# 737NG_CDU_SidePanel_v_01.net
KiCad netlist of a schematic drawn in EasyEDA
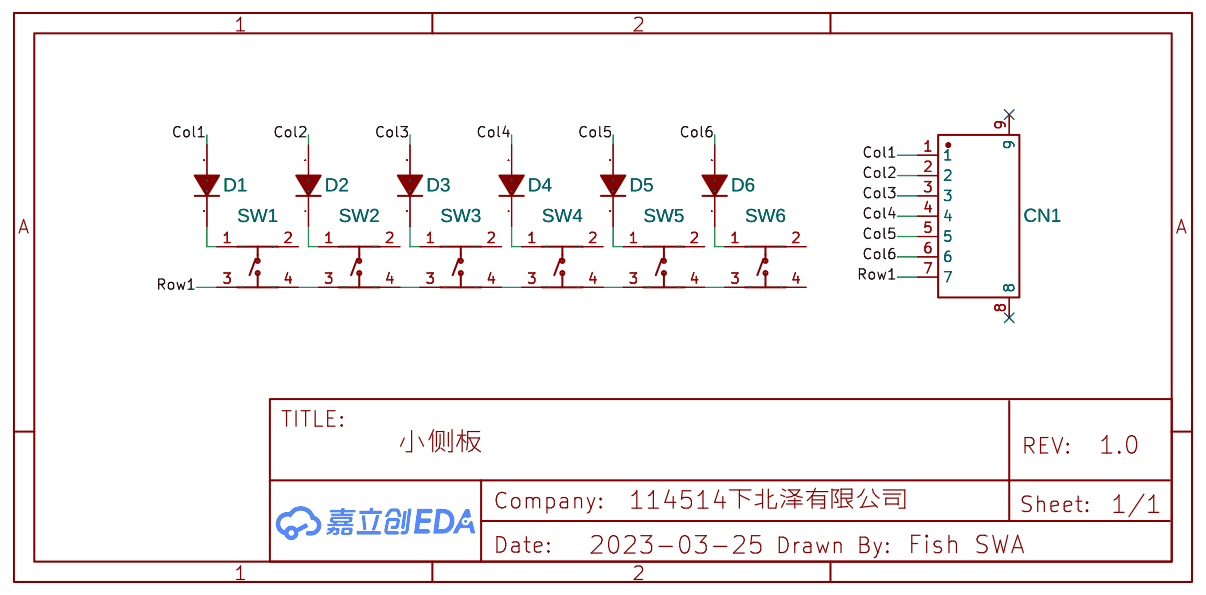
[diagram p0: schematic sheet]

(export (version "E")
  (design (tool "Eeschema 10.0.6"))
  (components
    (comp (ref "CN1")
      (value "A1002WR-S-7P")
      (fields (field (name "BOM_Supplier Part") "C239525"))
      (libsource (lib "") (part "A1002WR-S-7P"))
    )
    (comp (ref "D1")
      (value "1N4148WS T4")
      (fields (field (name "BOM_Manufacturer Part") "1N4148WS") (field (name "BOM_Supplier Part") "C2128"))
      (libsource (lib "") (part "1N4148WS T4"))
    )
    (comp (ref "D2")
      (value "1N4148WS T4")
      (fields (field (name "BOM_Manufacturer Part") "1N4148WS") (field (name "BOM_Supplier Part") "C2128"))
      (libsource (lib "") (part "1N4148WS T4"))
    )
    (comp (ref "D3")
      (value "1N4148WS T4")
      (fields (field (name "BOM_Manufacturer Part") "1N4148WS") (field (name "BOM_Supplier Part") "C2128"))
      (libsource (lib "") (part "1N4148WS T4"))
    )
    (comp (ref "D4")
      (value "1N4148WS T4")
      (fields (field (name "BOM_Manufacturer Part") "1N4148WS") (field (name "BOM_Supplier Part") "C2128"))
      (libsource (lib "") (part "1N4148WS T4"))
    )
    (comp (ref "D5")
      (value "1N4148WS T4")
      (fields (field (name "BOM_Manufacturer Part") "1N4148WS") (field (name "BOM_Supplier Part") "C2128"))
      (libsource (lib "") (part "1N4148WS T4"))
    )
    (comp (ref "D6")
      (value "1N4148WS T4")
      (fields (field (name "BOM_Manufacturer Part") "1N4148WS") (field (name "BOM_Supplier Part") "C2128"))
      (libsource (lib "") (part "1N4148WS T4"))
    )
    (comp (ref "SW1")
      (value "PTS525SM15SMTR2LFS")
      (fields (field (name "BOM_Supplier Part") "C221856"))
      (libsource (lib "") (part "PTS525SM15SMTR2LFS"))
    )
    (comp (ref "SW2")
      (value "PTS525SM15SMTR2LFS")
      (fields (field (name "BOM_Supplier Part") "C221856"))
      (libsource (lib "") (part "PTS525SM15SMTR2LFS"))
    )
    (comp (ref "SW3")
      (value "PTS525SM15SMTR2LFS")
      (fields (field (name "BOM_Supplier Part") "C221856"))
      (libsource (lib "") (part "PTS525SM15SMTR2LFS"))
    )
    (comp (ref "SW4")
      (value "PTS525SM15SMTR2LFS")
      (fields (field (name "BOM_Supplier Part") "C221856"))
      (libsource (lib "") (part "PTS525SM15SMTR2LFS"))
    )
    (comp (ref "SW5")
      (value "PTS525SM15SMTR2LFS")
      (fields (field (name "BOM_Supplier Part") "C221856"))
      (libsource (lib "") (part "PTS525SM15SMTR2LFS"))
    )
    (comp (ref "SW6")
      (value "PTS525SM15SMTR2LFS")
      (fields (field (name "BOM_Supplier Part") "C221856"))
      (libsource (lib "") (part "PTS525SM15SMTR2LFS"))
    )
  )
  (nets
    (net (code "1") (name "/Col1") (class "Default")
      (node (ref "CN1") (pin "1") (pinfunction "1_1") (pintype "unspecified"))
      (node (ref "D1") (pin "2") (pinfunction "A_2") (pintype "unspecified"))
    )
    (net (code "2") (name "/Col2") (class "Default")
      (node (ref "CN1") (pin "2") (pinfunction "2_2") (pintype "unspecified"))
      (node (ref "D2") (pin "2") (pinfunction "A_2") (pintype "unspecified"))
    )
    (net (code "3") (name "/Col3") (class "Default")
      (node (ref "CN1") (pin "3") (pinfunction "3_3") (pintype "unspecified"))
      (node (ref "D3") (pin "2") (pinfunction "A_2") (pintype "unspecified"))
    )
    (net (code "4") (name "/Col4") (class "Default")
      (node (ref "CN1") (pin "4") (pinfunction "4_4") (pintype "unspecified"))
      (node (ref "D4") (pin "2") (pinfunction "A_2") (pintype "unspecified"))
    )
    (net (code "5") (name "/Col5") (class "Default")
      (node (ref "CN1") (pin "5") (pinfunction "5_5") (pintype "unspecified"))
      (node (ref "D5") (pin "2") (pinfunction "A_2") (pintype "unspecified"))
    )
    (net (code "6") (name "/Col6") (class "Default")
      (node (ref "CN1") (pin "6") (pinfunction "6_6") (pintype "unspecified"))
      (node (ref "D6") (pin "2") (pinfunction "A_2") (pintype "unspecified"))
    )
    (net (code "7") (name "/Row1") (class "Default")
      (node (ref "CN1") (pin "7") (pinfunction "7_7") (pintype "unspecified"))
      (node (ref "SW1") (pin "3") (pinfunction "3_3") (pintype "unspecified"))
    )
    (net (code "8") (name "Net-(D1-K)") (class "Default")
      (node (ref "D1") (pin "1") (pinfunction "K_1") (pintype "unspecified"))
      (node (ref "SW1") (pin "1") (pinfunction "1_1") (pintype "unspecified"))
    )
    (net (code "9") (name "Net-(D2-K)") (class "Default")
      (node (ref "D2") (pin "1") (pinfunction "K_1") (pintype "unspecified"))
      (node (ref "SW2") (pin "1") (pinfunction "1_1") (pintype "unspecified"))
    )
    (net (code "10") (name "Net-(D3-K)") (class "Default")
      (node (ref "D3") (pin "1") (pinfunction "K_1") (pintype "unspecified"))
      (node (ref "SW3") (pin "1") (pinfunction "1_1") (pintype "unspecified"))
    )
    (net (code "11") (name "Net-(D4-K)") (class "Default")
      (node (ref "D4") (pin "1") (pinfunction "K_1") (pintype "unspecified"))
      (node (ref "SW4") (pin "1") (pinfunction "1_1") (pintype "unspecified"))
    )
    (net (code "12") (name "Net-(D5-K)") (class "Default")
      (node (ref "D5") (pin "1") (pinfunction "K_1") (pintype "unspecified"))
      (node (ref "SW5") (pin "1") (pinfunction "1_1") (pintype "unspecified"))
    )
    (net (code "13") (name "Net-(D6-K)") (class "Default")
      (node (ref "D6") (pin "1") (pinfunction "K_1") (pintype "unspecified"))
      (node (ref "SW6") (pin "1") (pinfunction "1_1") (pintype "unspecified"))
    )
    (net (code "14") (name "Net-(SW1-Pad4)") (class "Default")
      (node (ref "SW1") (pin "4") (pinfunction "4_4") (pintype "unspecified"))
      (node (ref "SW2") (pin "3") (pinfunction "3_3") (pintype "unspecified"))
    )
    (net (code "15") (name "Net-(SW2-Pad4)") (class "Default")
      (node (ref "SW2") (pin "4") (pinfunction "4_4") (pintype "unspecified"))
      (node (ref "SW3") (pin "3") (pinfunction "3_3") (pintype "unspecified"))
    )
    (net (code "16") (name "Net-(SW3-Pad4)") (class "Default")
      (node (ref "SW3") (pin "4") (pinfunction "4_4") (pintype "unspecified"))
      (node (ref "SW4") (pin "3") (pinfunction "3_3") (pintype "unspecified"))
    )
    (net (code "17") (name "Net-(SW4-Pad4)") (class "Default")
      (node (ref "SW4") (pin "4") (pinfunction "4_4") (pintype "unspecified"))
      (node (ref "SW5") (pin "3") (pinfunction "3_3") (pintype "unspecified"))
    )
    (net (code "18") (name "Net-(SW5-Pad4)") (class "Default")
      (node (ref "SW5") (pin "4") (pinfunction "4_4") (pintype "unspecified"))
      (node (ref "SW6") (pin "3") (pinfunction "3_3") (pintype "unspecified"))
    )
    (net (code "19") (name "unconnected-(CN1-Pad8)") (class "Default")
      (node (ref "CN1") (pin "8") (pinfunction "8_8") (pintype "unspecified+no_connect"))
    )
    (net (code "20") (name "unconnected-(CN1-Pad9)") (class "Default")
      (node (ref "CN1") (pin "9") (pinfunction "9_9") (pintype "unspecified+no_connect"))
    )
    (net (code "21") (name "unconnected-(SW1-Pad2)") (class "Default")
      (node (ref "SW1") (pin "2") (pinfunction "2_2") (pintype "unspecified"))
    )
    (net (code "22") (name "unconnected-(SW2-Pad2)") (class "Default")
      (node (ref "SW2") (pin "2") (pinfunction "2_2") (pintype "unspecified"))
    )
    (net (code "23") (name "unconnected-(SW3-Pad2)") (class "Default")
      (node (ref "SW3") (pin "2") (pinfunction "2_2") (pintype "unspecified"))
    )
    (net (code "24") (name "unconnected-(SW4-Pad2)") (class "Default")
      (node (ref "SW4") (pin "2") (pinfunction "2_2") (pintype "unspecified"))
    )
    (net (code "25") (name "unconnected-(SW5-Pad2)") (class "Default")
      (node (ref "SW5") (pin "2") (pinfunction "2_2") (pintype "unspecified"))
    )
    (net (code "26") (name "unconnected-(SW6-Pad2)") (class "Default")
      (node (ref "SW6") (pin "2") (pinfunction "2_2") (pintype "unspecified"))
    )
    (net (code "27") (name "unconnected-(SW6-Pad4)") (class "Default")
      (node (ref "SW6") (pin "4") (pinfunction "4_4") (pintype "unspecified"))
    )
  )
)
